# tinyogx360.net
KiCad netlist of a schematic drawn in EAGLE
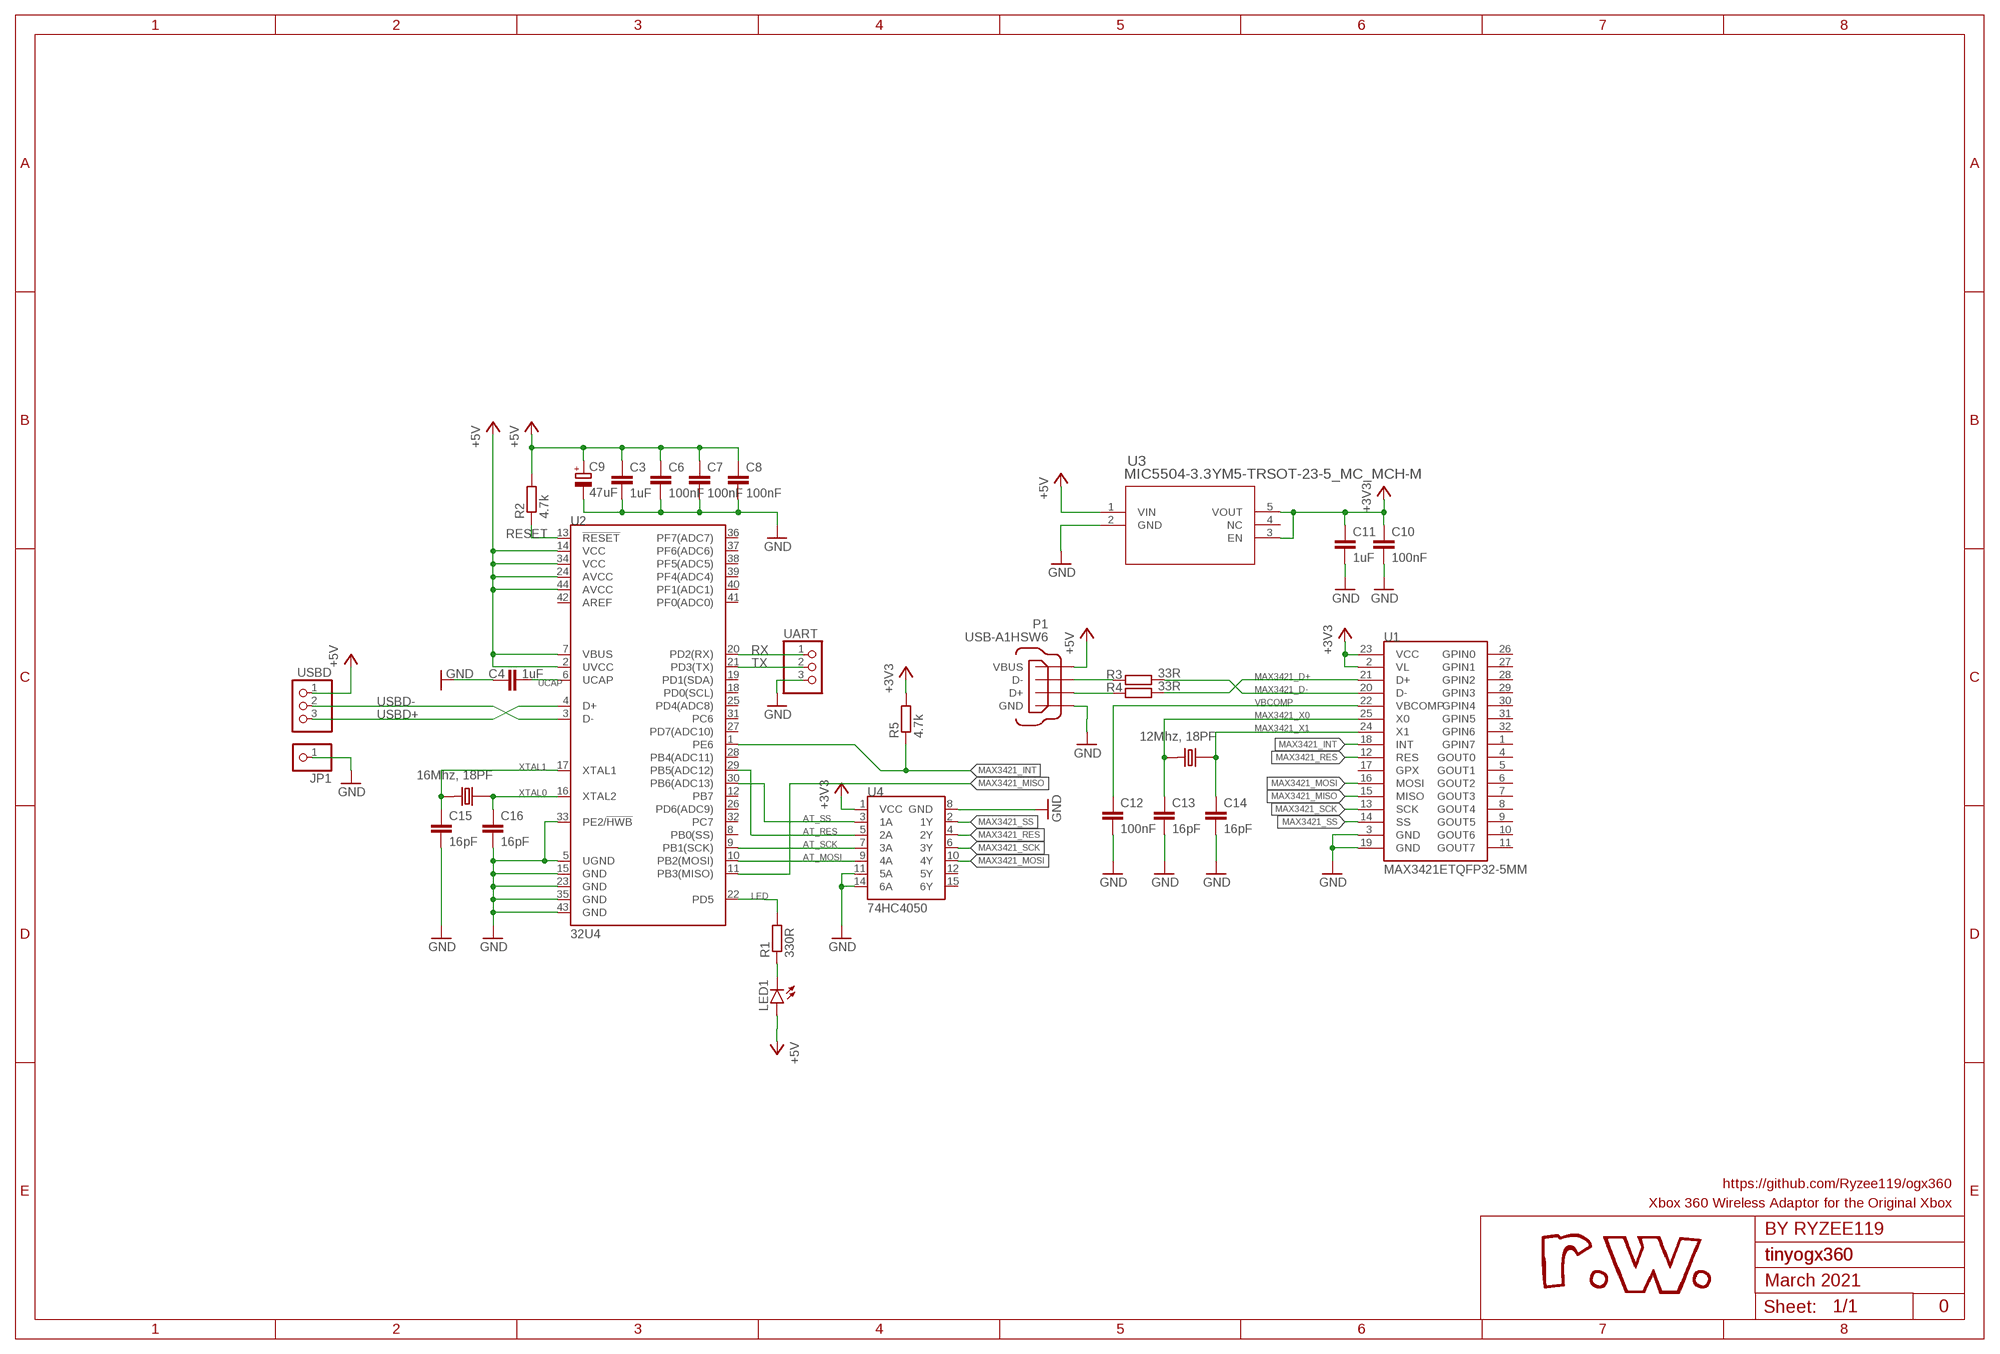
[diagram p0: schematic, sheet 1]

(export (version "E")
  (design (tool "Eeschema 10.0.6"))
  (components
    (comp (ref "C3")
      (value "1uF")
      (footprint "eagle-import:C0805K")
      (libsource (lib "eagle-import") (part "C-EUC0805K"))
    )
    (comp (ref "C4")
      (value "1uF")
      (footprint "eagle-import:C0805K")
      (libsource (lib "eagle-import") (part "C-EUC0805K"))
    )
    (comp (ref "C6")
      (value "100nF")
      (footprint "eagle-import:C0603K")
      (libsource (lib "eagle-import") (part "C-EUC0603K"))
    )
    (comp (ref "C7")
      (value "100nF")
      (footprint "eagle-import:C0603K")
      (libsource (lib "eagle-import") (part "C-EUC0603K"))
    )
    (comp (ref "C8")
      (value "100nF")
      (footprint "eagle-import:C0603K")
      (libsource (lib "eagle-import") (part "C-EUC0603K"))
    )
    (comp (ref "C9")
      (value "47uF")
      (footprint "eagle-import:153CLV-0505")
      (libsource (lib "eagle-import") (part "CPOL-EU153CLV-0505"))
    )
    (comp (ref "C10")
      (value "100nF")
      (footprint "eagle-import:C0603K")
      (libsource (lib "eagle-import") (part "C-EUC0603K"))
    )
    (comp (ref "C11")
      (value "1uF")
      (footprint "eagle-import:C0805K")
      (libsource (lib "eagle-import") (part "C-EUC0805K"))
    )
    (comp (ref "C12")
      (value "100nF")
      (footprint "eagle-import:C0603K")
      (libsource (lib "eagle-import") (part "C-EUC0603K"))
    )
    (comp (ref "C13")
      (value "16pF")
      (footprint "eagle-import:C0603K")
      (libsource (lib "eagle-import") (part "C-EUC0603K"))
    )
    (comp (ref "C14")
      (value "16pF")
      (footprint "eagle-import:C0603K")
      (libsource (lib "eagle-import") (part "C-EUC0603K"))
    )
    (comp (ref "C15")
      (value "16pF")
      (footprint "eagle-import:C0603K")
      (libsource (lib "eagle-import") (part "C-EUC0603K"))
    )
    (comp (ref "C16")
      (value "16pF")
      (footprint "eagle-import:C0603K")
      (libsource (lib "eagle-import") (part "C-EUC0603K"))
    )
    (comp (ref "JP1")
      (value "PINHD-1X1")
      (footprint "eagle-import:1X01")
      (libsource (lib "eagle-import") (part "PINHD-1X1"))
    )
    (comp (ref "LED1")
      (value "LEDCHIPLED_0603")
      (footprint "eagle-import:CHIPLED_0603")
      (libsource (lib "eagle-import") (part "LEDCHIPLED_0603"))
    )
    (comp (ref "P1")
      (value "USB-A1HSW6")
      (footprint "eagle-import:OST_USB-A1HSW6")
      (fields (field (name "DIGI-KEY_PART_NUMBER") "ED2989-ND") (field (name "MF") "On Shore"))
      (libsource (lib "eagle-import") (part "USB-A1HSW6"))
    )
    (comp (ref "R1")
      (value "330R")
      (footprint "eagle-import:R0603")
      (libsource (lib "eagle-import") (part "R-EU_R0603"))
    )
    (comp (ref "R2")
      (value "4.7k")
      (footprint "eagle-import:R0603")
      (libsource (lib "eagle-import") (part "R-EU_R0603"))
    )
    (comp (ref "R3")
      (value "33R")
      (footprint "eagle-import:R0603")
      (libsource (lib "eagle-import") (part "R-EU_R0603"))
    )
    (comp (ref "R4")
      (value "33R")
      (footprint "eagle-import:R0603")
      (libsource (lib "eagle-import") (part "R-EU_R0603"))
    )
    (comp (ref "R5")
      (value "4.7k")
      (footprint "eagle-import:R0603")
      (libsource (lib "eagle-import") (part "R-EU_R0603"))
    )
    (comp (ref "U1")
      (value "MAX3421ETQFP32-5MM")
      (footprint "eagle-import:TQFP32-5X5MM")
      (libsource (lib "eagle-import") (part "MAX3421ETQFP32-5MM"))
    )
    (comp (ref "U2")
      (value "32U4")
      (footprint "eagle-import:TQFP44")
      (libsource (lib "eagle-import") (part "ATMEGA32U4TQFP-44"))
    )
    (comp (ref "U3")
      (value "MIC5504-3.3YM5-TRSOT-23-5_MC_MCH-M")
      (footprint "eagle-import:SOT-23-5_MC_MCH-M")
      (fields
        (field (name "MANUFACTURER_PART_NUMBER") "MIC5504-3.3YM5-TR")
        (field (name "COPYRIGHT") "Copyright (C) 2018 Accelerated Designs. All rights reserved")
      )
      (libsource (lib "eagle-import") (part "MIC5504-3.3YM5-TRSOT-23-5_MC_MCH-M"))
    )
    (comp (ref "U4")
      (value "74HC4050")
      (footprint "eagle-import:SO16")
      (libsource (lib "eagle-import") (part "HEX_CONVERTER"))
    )
    (comp (ref "UART")
      (value "PINHD-1X3")
      (footprint "eagle-import:1X03")
      (libsource (lib "eagle-import") (part "PINHD-1X3"))
    )
    (comp (ref "USBD")
      (value "PINHD-1X3")
      (footprint "eagle-import:1X03")
      (libsource (lib "eagle-import") (part "PINHD-1X3"))
    )
    (comp (ref "Y1")
      (value "12Mhz, 18PF")
      (footprint "eagle-import:XTAL_ECS-250-18-5PX-JEM-TR")
      (fields
        (field (name "DIGI-KEY_PART_NUMBER") "XC2083CT-ND")
        (field (name "MF") "ECS Inc.")
        (field (name "MP") "ECS-250-18-5PX-JEM-TR")
      )
      (libsource (lib "eagle-import") (part "ECS-250-18-5PX-JEM-TR"))
    )
    (comp (ref "Y2")
      (value "16Mhz, 18PF")
      (footprint "eagle-import:XTAL_ECS-250-18-5PX-JEM-TR")
      (fields
        (field (name "DIGI-KEY_PART_NUMBER") "XC2083CT-ND")
        (field (name "MF") "ECS Inc.")
        (field (name "MP") "ECS-250-18-5PX-JEM-TR")
      )
      (libsource (lib "eagle-import") (part "ECS-250-18-5PX-JEM-TR"))
    )
  )
  (nets
    (net (code "1") (name "+3V3") (class "Default")
      (node (ref "C10") (pin "1") (pinfunction "1_1") (pintype "passive"))
      (node (ref "C11") (pin "1") (pinfunction "1_1") (pintype "passive"))
      (node (ref "R5") (pin "2") (pinfunction "2_2") (pintype "passive"))
      (node (ref "U1") (pin "2") (pinfunction "VL_2") (pintype "bidirectional"))
      (node (ref "U1") (pin "23") (pinfunction "VCC_23") (pintype "bidirectional"))
      (node (ref "U3") (pin "3") (pinfunction "EN_3") (pintype "input"))
      (node (ref "U3") (pin "5") (pinfunction "VOUT_5") (pintype "output"))
      (node (ref "U4") (pin "1") (pinfunction "VCC_1") (pintype "bidirectional"))
    )
    (net (code "2") (name "+5V") (class "Default")
      (node (ref "C3") (pin "1") (pinfunction "1_1") (pintype "passive"))
      (node (ref "C6") (pin "1") (pinfunction "1_1") (pintype "passive"))
      (node (ref "C7") (pin "1") (pinfunction "1_1") (pintype "passive"))
      (node (ref "C8") (pin "1") (pinfunction "1_1") (pintype "passive"))
      (node (ref "C9") (pin "+") (pinfunction "+_+") (pintype "passive"))
      (node (ref "LED1") (pin "A") (pinfunction "A_A") (pintype "passive"))
      (node (ref "P1") (pin "1") (pinfunction "VBUS_1") (pintype "power_in"))
      (node (ref "R2") (pin "2") (pinfunction "2_2") (pintype "passive"))
      (node (ref "U2") (pin "14") (pinfunction "VCC_14") (pintype "bidirectional"))
      (node (ref "U2") (pin "2") (pinfunction "UVCC_2") (pintype "bidirectional"))
      (node (ref "U2") (pin "24") (pinfunction "AVCC_24") (pintype "bidirectional"))
      (node (ref "U2") (pin "34") (pinfunction "VCC_34") (pintype "bidirectional"))
      (node (ref "U2") (pin "44") (pinfunction "AVCC_44") (pintype "bidirectional"))
      (node (ref "U2") (pin "7") (pinfunction "VBUS_7") (pintype "bidirectional"))
      (node (ref "U3") (pin "1") (pinfunction "VIN_1") (pintype "input"))
      (node (ref "USBD") (pin "1") (pinfunction "1_1") (pintype "passive"))
    )
    (net (code "3") (name "/AT_MOSI") (class "Default")
      (node (ref "U2") (pin "10") (pinfunction "PB2(MOSI)_10") (pintype "bidirectional"))
      (node (ref "U4") (pin "9") (pinfunction "4A_9") (pintype "bidirectional"))
    )
    (net (code "4") (name "/AT_RES") (class "Default")
      (node (ref "U2") (pin "29") (pinfunction "PB5(ADC12)_29") (pintype "bidirectional"))
      (node (ref "U4") (pin "5") (pinfunction "2A_5") (pintype "bidirectional"))
    )
    (net (code "5") (name "/AT_SCK") (class "Default")
      (node (ref "U2") (pin "9") (pinfunction "PB1(SCK)_9") (pintype "bidirectional"))
      (node (ref "U4") (pin "7") (pinfunction "3A_7") (pintype "bidirectional"))
    )
    (net (code "6") (name "/AT_SS") (class "Default")
      (node (ref "U2") (pin "30") (pinfunction "PB6(ADC13)_30") (pintype "bidirectional"))
      (node (ref "U4") (pin "3") (pinfunction "1A_3") (pintype "bidirectional"))
    )
    (net (code "7") (name "/LED") (class "Default")
      (node (ref "R1") (pin "2") (pinfunction "2_2") (pintype "passive"))
      (node (ref "U2") (pin "22") (pinfunction "PD5_22") (pintype "bidirectional"))
    )
    (net (code "8") (name "/MAX3421_D+") (class "Default")
      (node (ref "R4") (pin "2") (pinfunction "2_2") (pintype "passive"))
      (node (ref "U1") (pin "21") (pinfunction "D+_21") (pintype "bidirectional"))
    )
    (net (code "9") (name "/MAX3421_D-") (class "Default")
      (node (ref "R3") (pin "2") (pinfunction "2_2") (pintype "passive"))
      (node (ref "U1") (pin "20") (pinfunction "D-_20") (pintype "bidirectional"))
    )
    (net (code "10") (name "/MAX3421_X0") (class "Default")
      (node (ref "C13") (pin "1") (pinfunction "1_1") (pintype "passive"))
      (node (ref "U1") (pin "25") (pinfunction "X0_25") (pintype "bidirectional"))
      (node (ref "Y1") (pin "2") (pinfunction "2_2") (pintype "passive"))
    )
    (net (code "11") (name "/MAX3421_X1") (class "Default")
      (node (ref "C14") (pin "1") (pinfunction "1_1") (pintype "passive"))
      (node (ref "U1") (pin "24") (pinfunction "X1_24") (pintype "bidirectional"))
      (node (ref "Y1") (pin "1") (pinfunction "1_1") (pintype "passive"))
    )
    (net (code "12") (name "/RESET") (class "Default")
      (node (ref "R2") (pin "1") (pinfunction "1_1") (pintype "passive"))
      (node (ref "U2") (pin "13") (pinfunction "~{RESET}_13") (pintype "bidirectional"))
    )
    (net (code "13") (name "/RX") (class "Default")
      (node (ref "U2") (pin "20") (pinfunction "PD2(RX)_20") (pintype "bidirectional"))
      (node (ref "UART") (pin "1") (pinfunction "1_1") (pintype "passive"))
    )
    (net (code "14") (name "/TX") (class "Default")
      (node (ref "U2") (pin "21") (pinfunction "PD3(TX)_21") (pintype "bidirectional"))
      (node (ref "UART") (pin "2") (pinfunction "2_2") (pintype "passive"))
    )
    (net (code "15") (name "/UCAP") (class "Default")
      (node (ref "C4") (pin "2") (pinfunction "2_2") (pintype "passive"))
      (node (ref "U2") (pin "6") (pinfunction "UCAP_6") (pintype "bidirectional"))
    )
    (net (code "16") (name "/USBD+") (class "Default")
      (node (ref "U2") (pin "4") (pinfunction "D+_4") (pintype "bidirectional"))
      (node (ref "USBD") (pin "3") (pinfunction "3_3") (pintype "passive"))
    )
    (net (code "17") (name "/USBD-") (class "Default")
      (node (ref "U2") (pin "3") (pinfunction "D-_3") (pintype "bidirectional"))
      (node (ref "USBD") (pin "2") (pinfunction "2_2") (pintype "passive"))
    )
    (net (code "18") (name "/VBCOMP") (class "Default")
      (node (ref "C12") (pin "1") (pinfunction "1_1") (pintype "passive"))
      (node (ref "U1") (pin "22") (pinfunction "VBCOMP_22") (pintype "bidirectional"))
    )
    (net (code "19") (name "/XTAL0") (class "Default")
      (node (ref "C16") (pin "1") (pinfunction "1_1") (pintype "passive"))
      (node (ref "U2") (pin "16") (pinfunction "XTAL2_16") (pintype "bidirectional"))
      (node (ref "Y2") (pin "1") (pinfunction "1_1") (pintype "passive"))
    )
    (net (code "20") (name "/XTAL1") (class "Default")
      (node (ref "C15") (pin "1") (pinfunction "1_1") (pintype "passive"))
      (node (ref "U2") (pin "17") (pinfunction "XTAL1_17") (pintype "bidirectional"))
      (node (ref "Y2") (pin "2") (pinfunction "2_2") (pintype "passive"))
    )
    (net (code "21") (name "GND") (class "Default")
      (node (ref "C10") (pin "2") (pinfunction "2_2") (pintype "passive"))
      (node (ref "C11") (pin "2") (pinfunction "2_2") (pintype "passive"))
      (node (ref "C12") (pin "2") (pinfunction "2_2") (pintype "passive"))
      (node (ref "C13") (pin "2") (pinfunction "2_2") (pintype "passive"))
      (node (ref "C14") (pin "2") (pinfunction "2_2") (pintype "passive"))
      (node (ref "C15") (pin "2") (pinfunction "2_2") (pintype "passive"))
      (node (ref "C16") (pin "2") (pinfunction "2_2") (pintype "passive"))
      (node (ref "C3") (pin "2") (pinfunction "2_2") (pintype "passive"))
      (node (ref "C4") (pin "1") (pinfunction "1_1") (pintype "passive"))
      (node (ref "C6") (pin "2") (pinfunction "2_2") (pintype "passive"))
      (node (ref "C7") (pin "2") (pinfunction "2_2") (pintype "passive"))
      (node (ref "C8") (pin "2") (pinfunction "2_2") (pintype "passive"))
      (node (ref "C9") (pin "-") (pinfunction "-_-") (pintype "passive"))
      (node (ref "JP1") (pin "1") (pinfunction "1_1") (pintype "passive"))
      (node (ref "P1") (pin "4") (pinfunction "GND_4") (pintype "power_in"))
      (node (ref "U1") (pin "19") (pinfunction "GND_19") (pintype "bidirectional"))
      (node (ref "U1") (pin "3") (pinfunction "GND_3") (pintype "bidirectional"))
      (node (ref "U2") (pin "15") (pinfunction "GND_15") (pintype "bidirectional"))
      (node (ref "U2") (pin "23") (pinfunction "GND_23") (pintype "bidirectional"))
      (node (ref "U2") (pin "33") (pinfunction "PE2/~{HWB}_33") (pintype "bidirectional"))
      (node (ref "U2") (pin "35") (pinfunction "GND_35") (pintype "bidirectional"))
      (node (ref "U2") (pin "43") (pinfunction "GND_43") (pintype "bidirectional"))
      (node (ref "U2") (pin "5") (pinfunction "UGND_5") (pintype "bidirectional"))
      (node (ref "U3") (pin "2") (pinfunction "GND_2") (pintype "power_in"))
      (node (ref "U4") (pin "11") (pinfunction "5A_11") (pintype "bidirectional"))
      (node (ref "U4") (pin "14") (pinfunction "6A_14") (pintype "bidirectional"))
      (node (ref "U4") (pin "8") (pinfunction "GND_8") (pintype "bidirectional"))
      (node (ref "UART") (pin "3") (pinfunction "3_3") (pintype "passive"))
    )
    (net (code "22") (name "MAX3421_INT") (class "Default")
      (node (ref "R5") (pin "1") (pinfunction "1_1") (pintype "passive"))
      (node (ref "U1") (pin "18") (pinfunction "INT_18") (pintype "bidirectional"))
      (node (ref "U2") (pin "1") (pinfunction "PE6_1") (pintype "bidirectional"))
    )
    (net (code "23") (name "MAX3421_MISO") (class "Default")
      (node (ref "U1") (pin "15") (pinfunction "MISO_15") (pintype "bidirectional"))
      (node (ref "U2") (pin "11") (pinfunction "PB3(MISO)_11") (pintype "bidirectional"))
    )
    (net (code "24") (name "MAX3421_MOSI") (class "Default")
      (node (ref "U1") (pin "16") (pinfunction "MOSI_16") (pintype "bidirectional"))
      (node (ref "U4") (pin "10") (pinfunction "4Y_10") (pintype "bidirectional"))
    )
    (net (code "25") (name "MAX3421_RES") (class "Default")
      (node (ref "U1") (pin "12") (pinfunction "RES_12") (pintype "bidirectional"))
      (node (ref "U4") (pin "4") (pinfunction "2Y_4") (pintype "bidirectional"))
    )
    (net (code "26") (name "MAX3421_SCK") (class "Default")
      (node (ref "U1") (pin "13") (pinfunction "SCK_13") (pintype "bidirectional"))
      (node (ref "U4") (pin "6") (pinfunction "3Y_6") (pintype "bidirectional"))
    )
    (net (code "27") (name "MAX3421_SS") (class "Default")
      (node (ref "U1") (pin "14") (pinfunction "SS_14") (pintype "bidirectional"))
      (node (ref "U4") (pin "2") (pinfunction "1Y_2") (pintype "bidirectional"))
    )
    (net (code "28") (name "Net-(LED1-PadC)") (class "Default")
      (node (ref "LED1") (pin "C") (pinfunction "C_C") (pintype "passive"))
      (node (ref "R1") (pin "1") (pinfunction "1_1") (pintype "passive"))
    )
    (net (code "29") (name "Net-(P1-D+)") (class "Default")
      (node (ref "P1") (pin "3") (pinfunction "D+_3") (pintype "bidirectional"))
      (node (ref "R4") (pin "1") (pinfunction "1_1") (pintype "passive"))
    )
    (net (code "30") (name "Net-(P1-D-)") (class "Default")
      (node (ref "P1") (pin "2") (pinfunction "D-_2") (pintype "bidirectional"))
      (node (ref "R3") (pin "1") (pinfunction "1_1") (pintype "passive"))
    )
    (net (code "31") (name "unconnected-(U1-GOUT0-Pad4)") (class "Default")
      (node (ref "U1") (pin "4") (pinfunction "GOUT0_4") (pintype "bidirectional"))
    )
    (net (code "32") (name "unconnected-(U1-GOUT1-Pad5)") (class "Default")
      (node (ref "U1") (pin "5") (pinfunction "GOUT1_5") (pintype "bidirectional"))
    )
    (net (code "33") (name "unconnected-(U1-GOUT2-Pad6)") (class "Default")
      (node (ref "U1") (pin "6") (pinfunction "GOUT2_6") (pintype "bidirectional"))
    )
    (net (code "34") (name "unconnected-(U1-GOUT3-Pad7)") (class "Default")
      (node (ref "U1") (pin "7") (pinfunction "GOUT3_7") (pintype "bidirectional"))
    )
    (net (code "35") (name "unconnected-(U1-GOUT4-Pad8)") (class "Default")
      (node (ref "U1") (pin "8") (pinfunction "GOUT4_8") (pintype "bidirectional"))
    )
    (net (code "36") (name "unconnected-(U1-GOUT5-Pad9)") (class "Default")
      (node (ref "U1") (pin "9") (pinfunction "GOUT5_9") (pintype "bidirectional"))
    )
    (net (code "37") (name "unconnected-(U1-GOUT6-Pad10)") (class "Default")
      (node (ref "U1") (pin "10") (pinfunction "GOUT6_10") (pintype "bidirectional"))
    )
    (net (code "38") (name "unconnected-(U1-GOUT7-Pad11)") (class "Default")
      (node (ref "U1") (pin "11") (pinfunction "GOUT7_11") (pintype "bidirectional"))
    )
    (net (code "39") (name "unconnected-(U1-GPIN0-Pad26)") (class "Default")
      (node (ref "U1") (pin "26") (pinfunction "GPIN0_26") (pintype "bidirectional"))
    )
    (net (code "40") (name "unconnected-(U1-GPIN1-Pad27)") (class "Default")
      (node (ref "U1") (pin "27") (pinfunction "GPIN1_27") (pintype "bidirectional"))
    )
    (net (code "41") (name "unconnected-(U1-GPIN2-Pad28)") (class "Default")
      (node (ref "U1") (pin "28") (pinfunction "GPIN2_28") (pintype "bidirectional"))
    )
    (net (code "42") (name "unconnected-(U1-GPIN3-Pad29)") (class "Default")
      (node (ref "U1") (pin "29") (pinfunction "GPIN3_29") (pintype "bidirectional"))
    )
    (net (code "43") (name "unconnected-(U1-GPIN4-Pad30)") (class "Default")
      (node (ref "U1") (pin "30") (pinfunction "GPIN4_30") (pintype "bidirectional"))
    )
    (net (code "44") (name "unconnected-(U1-GPIN5-Pad31)") (class "Default")
      (node (ref "U1") (pin "31") (pinfunction "GPIN5_31") (pintype "bidirectional"))
    )
    (net (code "45") (name "unconnected-(U1-GPIN6-Pad32)") (class "Default")
      (node (ref "U1") (pin "32") (pinfunction "GPIN6_32") (pintype "bidirectional"))
    )
    (net (code "46") (name "unconnected-(U1-GPIN7-Pad1)") (class "Default")
      (node (ref "U1") (pin "1") (pinfunction "GPIN7_1") (pintype "bidirectional"))
    )
    (net (code "47") (name "unconnected-(U1-GPX-Pad17)") (class "Default")
      (node (ref "U1") (pin "17") (pinfunction "GPX_17") (pintype "bidirectional"))
    )
    (net (code "48") (name "unconnected-(U2-AREF-Pad42)") (class "Default")
      (node (ref "U2") (pin "42") (pinfunction "AREF_42") (pintype "bidirectional"))
    )
    (net (code "49") (name "unconnected-(U2-PB0(SS)-Pad8)") (class "Default")
      (node (ref "U2") (pin "8") (pinfunction "PB0(SS)_8") (pintype "bidirectional"))
    )
    (net (code "50") (name "unconnected-(U2-PB4(ADC11)-Pad28)") (class "Default")
      (node (ref "U2") (pin "28") (pinfunction "PB4(ADC11)_28") (pintype "bidirectional"))
    )
    (net (code "51") (name "unconnected-(U2-PB7-Pad12)") (class "Default")
      (node (ref "U2") (pin "12") (pinfunction "PB7_12") (pintype "bidirectional"))
    )
    (net (code "52") (name "unconnected-(U2-PC6-Pad31)") (class "Default")
      (node (ref "U2") (pin "31") (pinfunction "PC6_31") (pintype "bidirectional"))
    )
    (net (code "53") (name "unconnected-(U2-PC7-Pad32)") (class "Default")
      (node (ref "U2") (pin "32") (pinfunction "PC7_32") (pintype "bidirectional"))
    )
    (net (code "54") (name "unconnected-(U2-PD0(SCL)-Pad18)") (class "Default")
      (node (ref "U2") (pin "18") (pinfunction "PD0(SCL)_18") (pintype "bidirectional"))
    )
    (net (code "55") (name "unconnected-(U2-PD1(SDA)-Pad19)") (class "Default")
      (node (ref "U2") (pin "19") (pinfunction "PD1(SDA)_19") (pintype "bidirectional"))
    )
    (net (code "56") (name "unconnected-(U2-PD4(ADC8)-Pad25)") (class "Default")
      (node (ref "U2") (pin "25") (pinfunction "PD4(ADC8)_25") (pintype "bidirectional"))
    )
    (net (code "57") (name "unconnected-(U2-PD6(ADC9)-Pad26)") (class "Default")
      (node (ref "U2") (pin "26") (pinfunction "PD6(ADC9)_26") (pintype "bidirectional"))
    )
    (net (code "58") (name "unconnected-(U2-PD7(ADC10)-Pad27)") (class "Default")
      (node (ref "U2") (pin "27") (pinfunction "PD7(ADC10)_27") (pintype "bidirectional"))
    )
    (net (code "59") (name "unconnected-(U2-PF0(ADC0)-Pad41)") (class "Default")
      (node (ref "U2") (pin "41") (pinfunction "PF0(ADC0)_41") (pintype "bidirectional"))
    )
    (net (code "60") (name "unconnected-(U2-PF1(ADC1)-Pad40)") (class "Default")
      (node (ref "U2") (pin "40") (pinfunction "PF1(ADC1)_40") (pintype "bidirectional"))
    )
    (net (code "61") (name "unconnected-(U2-PF4(ADC4)-Pad39)") (class "Default")
      (node (ref "U2") (pin "39") (pinfunction "PF4(ADC4)_39") (pintype "bidirectional"))
    )
    (net (code "62") (name "unconnected-(U2-PF5(ADC5)-Pad38)") (class "Default")
      (node (ref "U2") (pin "38") (pinfunction "PF5(ADC5)_38") (pintype "bidirectional"))
    )
    (net (code "63") (name "unconnected-(U2-PF6(ADC6)-Pad37)") (class "Default")
      (node (ref "U2") (pin "37") (pinfunction "PF6(ADC6)_37") (pintype "bidirectional"))
    )
    (net (code "64") (name "unconnected-(U2-PF7(ADC7)-Pad36)") (class "Default")
      (node (ref "U2") (pin "36") (pinfunction "PF7(ADC7)_36") (pintype "bidirectional"))
    )
    (net (code "65") (name "unconnected-(U3-NC-Pad4)") (class "Default")
      (node (ref "U3") (pin "4") (pinfunction "NC_4") (pintype "no_connect"))
    )
    (net (code "66") (name "unconnected-(U4-5Y-Pad12)") (class "Default")
      (node (ref "U4") (pin "12") (pinfunction "5Y_12") (pintype "bidirectional"))
    )
    (net (code "67") (name "unconnected-(U4-6Y-Pad15)") (class "Default")
      (node (ref "U4") (pin "15") (pinfunction "6Y_15") (pintype "bidirectional"))
    )
  )
)
